# J-Flash.net
KiCad netlist of a schematic drawn in Altium Designer
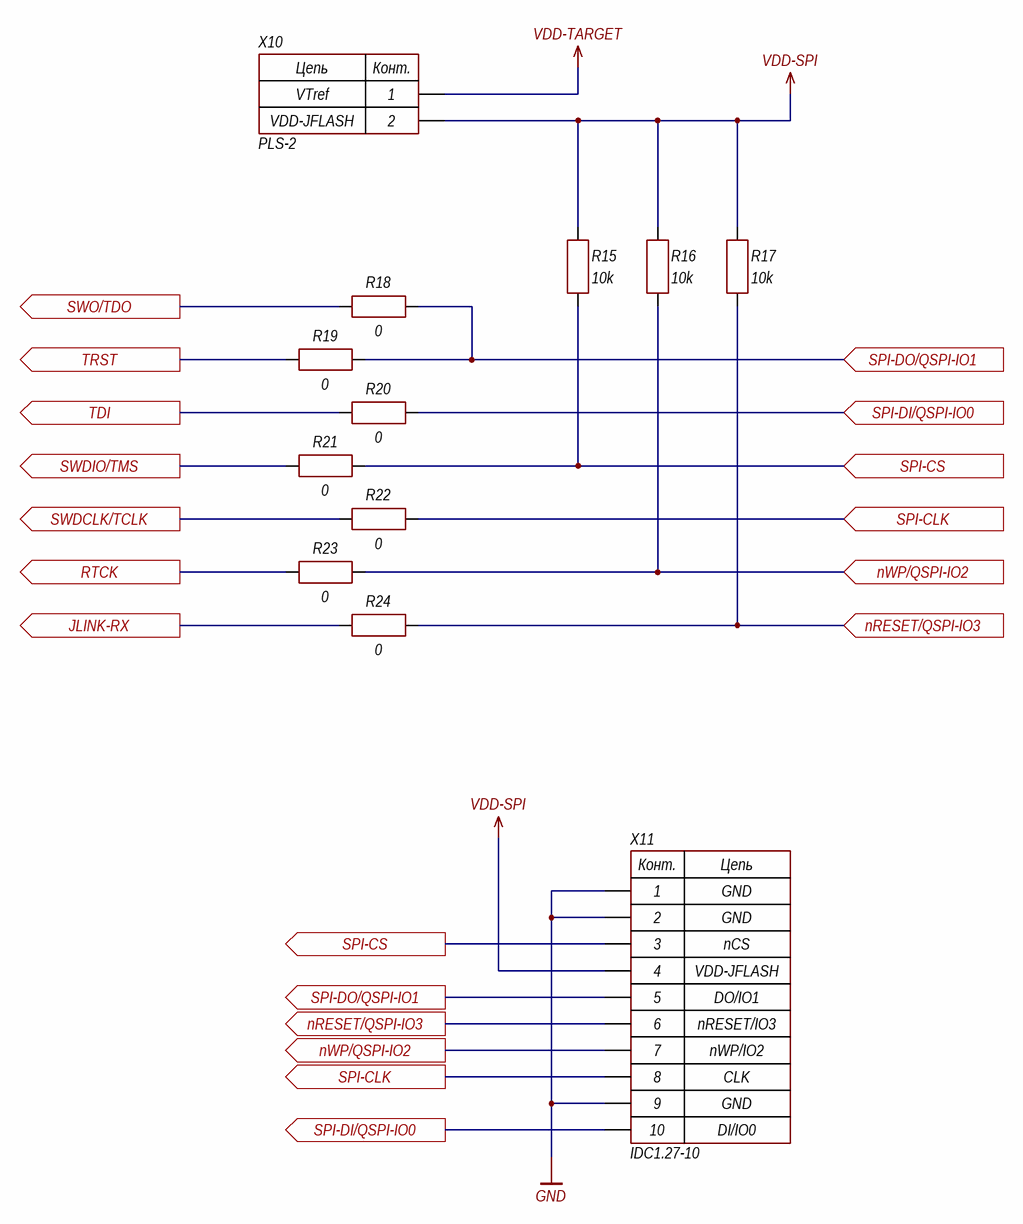
[diagram p0: J-Flash.SchDoc]

(export (version "E")
  (design (tool "Eeschema 10.0.6"))
  (components
    (comp (ref "R15") (value "10k") (footprint "CH0402R") (libsource (lib "") (part "Resistor_1")))
    (comp (ref "R16") (value "10k") (footprint "CH0402R") (libsource (lib "") (part "Resistor_1")))
    (comp (ref "R17") (value "10k") (footprint "CH0402R") (libsource (lib "") (part "Resistor_1")))
    (comp (ref "R18") (value "0") (footprint "CH0402R") (libsource (lib "Discrete") (part "Resistor")))
    (comp (ref "R19") (value "0") (footprint "CH0402R") (libsource (lib "Discrete") (part "Resistor")))
    (comp (ref "R20") (value "0") (footprint "CH0402R") (libsource (lib "Discrete") (part "Resistor")))
    (comp (ref "R21") (value "0") (footprint "CH0402R") (libsource (lib "Discrete") (part "Resistor")))
    (comp (ref "R22") (value "0") (footprint "CH0402R") (libsource (lib "Discrete") (part "Resistor")))
    (comp (ref "R23") (value "0") (footprint "CH0402R") (libsource (lib "Discrete") (part "Resistor")))
    (comp (ref "R24") (value "0") (footprint "CH0402R") (libsource (lib "Discrete") (part "Resistor")))
    (comp (ref "X10")
      (value "PLS-2")
      (footprint "CON: PLS-2")
      (libsource (lib "Connectors") (part "2-Connector"))
    )
    (comp (ref "X11")
      (value "IDC1.27-10")
      (footprint "CON: IDC1.27-10")
      (libsource (lib "Connectors") (part "10-Connector"))
    )
  )
  (nets
    (net (code "1") (name "/JLINK-RX") (class "Default")
      (node (ref "R24") (pin "1") (pinfunction "1_1") (pintype "passive"))
    )
    (net (code "2") (name "/RTCK") (class "Default")
      (node (ref "R23") (pin "1") (pinfunction "1_1") (pintype "passive"))
    )
    (net (code "3") (name "/SPI-CLK") (class "Default")
      (node (ref "R22") (pin "2") (pinfunction "2_2") (pintype "passive"))
      (node (ref "X11") (pin "8") (pinfunction "8_8") (pintype "passive"))
    )
    (net (code "4") (name "/SPI-CS") (class "Default")
      (node (ref "R15") (pin "1") (pinfunction "1_1") (pintype "passive"))
      (node (ref "R21") (pin "2") (pinfunction "2_2") (pintype "passive"))
      (node (ref "X11") (pin "3") (pinfunction "3_3") (pintype "passive"))
    )
    (net (code "5") (name "/SPI-DI{slash}QSPI-IO0") (class "Default")
      (node (ref "R20") (pin "2") (pinfunction "2_2") (pintype "passive"))
      (node (ref "X11") (pin "10") (pinfunction "10_10") (pintype "passive"))
    )
    (net (code "6") (name "/SPI-DO{slash}QSPI-IO1") (class "Default")
      (node (ref "R18") (pin "2") (pinfunction "2_2") (pintype "passive"))
      (node (ref "R19") (pin "2") (pinfunction "2_2") (pintype "passive"))
      (node (ref "X11") (pin "5") (pinfunction "5_5") (pintype "passive"))
    )
    (net (code "7") (name "/SWDCLK{slash}TCLK") (class "Default")
      (node (ref "R22") (pin "1") (pinfunction "1_1") (pintype "passive"))
    )
    (net (code "8") (name "/SWDIO{slash}TMS") (class "Default")
      (node (ref "R21") (pin "1") (pinfunction "1_1") (pintype "passive"))
    )
    (net (code "9") (name "/SWO{slash}TDO") (class "Default")
      (node (ref "R18") (pin "1") (pinfunction "1_1") (pintype "passive"))
    )
    (net (code "10") (name "/TDI") (class "Default")
      (node (ref "R20") (pin "1") (pinfunction "1_1") (pintype "passive"))
    )
    (net (code "11") (name "/TRST") (class "Default")
      (node (ref "R19") (pin "1") (pinfunction "1_1") (pintype "passive"))
    )
    (net (code "12") (name "/nRESET{slash}QSPI-IO3") (class "Default")
      (node (ref "R17") (pin "1") (pinfunction "1_1") (pintype "passive"))
      (node (ref "R24") (pin "2") (pinfunction "2_2") (pintype "passive"))
      (node (ref "X11") (pin "6") (pinfunction "6_6") (pintype "passive"))
    )
    (net (code "13") (name "/nWP{slash}QSPI-IO2") (class "Default")
      (node (ref "R16") (pin "1") (pinfunction "1_1") (pintype "passive"))
      (node (ref "R23") (pin "2") (pinfunction "2_2") (pintype "passive"))
      (node (ref "X11") (pin "7") (pinfunction "7_7") (pintype "passive"))
    )
    (net (code "14") (name "GND") (class "Default")
      (node (ref "X11") (pin "1") (pinfunction "1_1") (pintype "passive"))
      (node (ref "X11") (pin "2") (pinfunction "2_2") (pintype "passive"))
      (node (ref "X11") (pin "9") (pinfunction "9_9") (pintype "passive"))
    )
    (net (code "15") (name "VDD-SPI") (class "Default")
      (node (ref "R15") (pin "2") (pinfunction "2_2") (pintype "passive"))
      (node (ref "R16") (pin "2") (pinfunction "2_2") (pintype "passive"))
      (node (ref "R17") (pin "2") (pinfunction "2_2") (pintype "passive"))
      (node (ref "X10") (pin "2") (pinfunction "2_2") (pintype "passive"))
      (node (ref "X11") (pin "4") (pinfunction "4_4") (pintype "passive"))
    )
    (net (code "16") (name "VDD-TARGET") (class "Default")
      (node (ref "X10") (pin "1") (pinfunction "1_1") (pintype "passive"))
    )
  )
)
